# Battery-Switch.net
KiCad netlist of a schematic drawn in Altium Designer
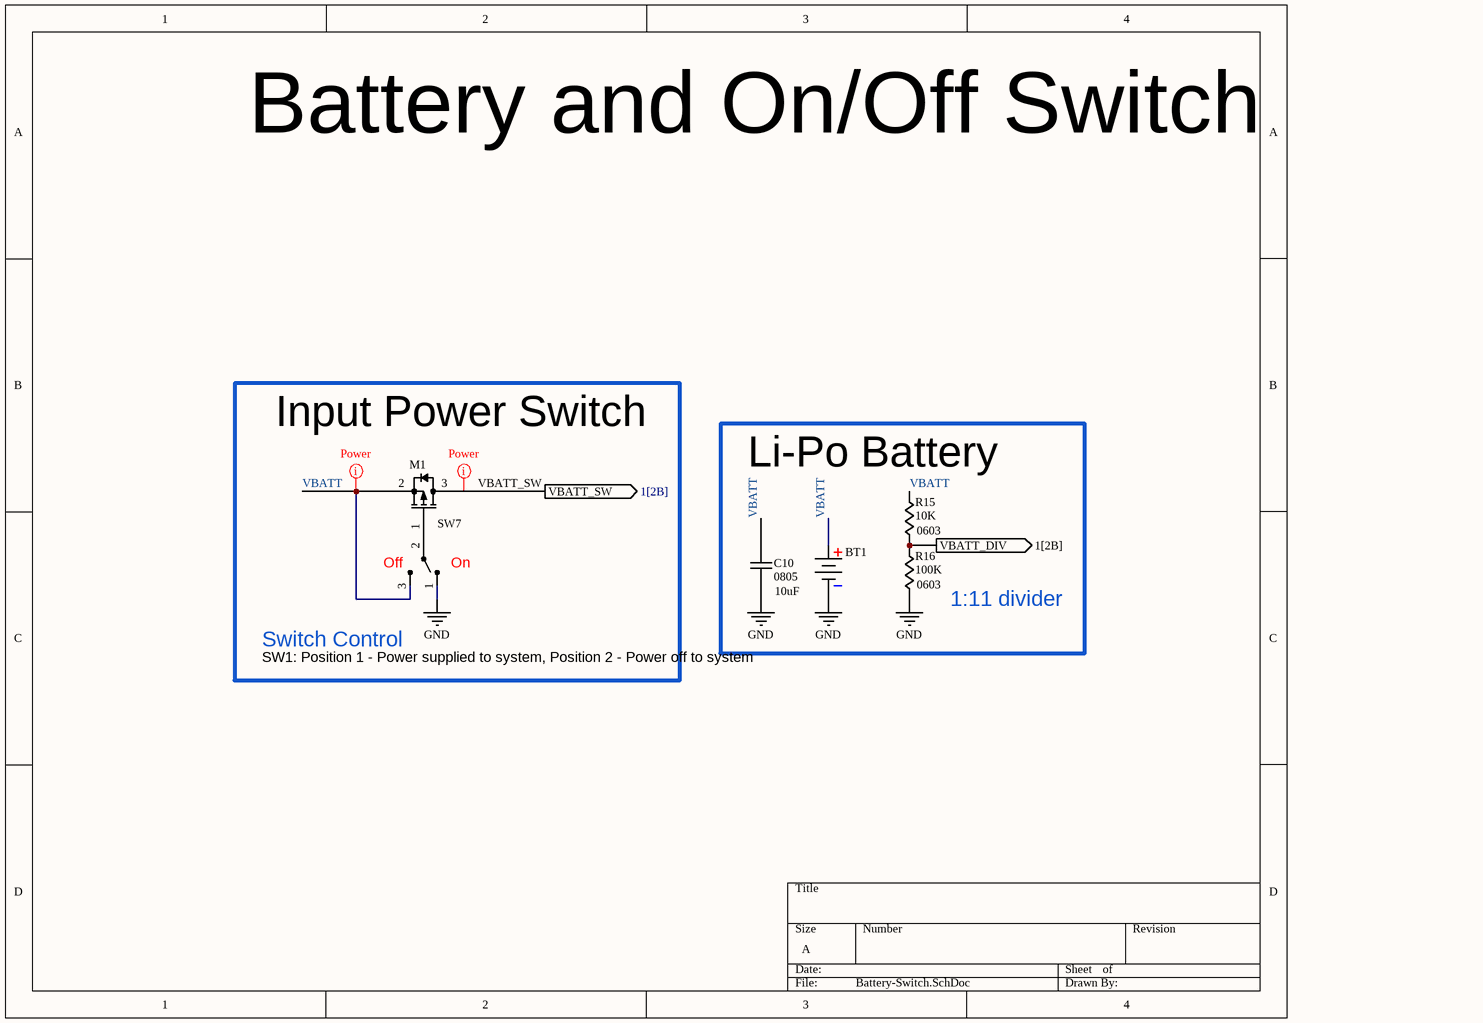
[diagram p0: Battery-Switch.SchDoc]

(export (version "E")
  (design (tool "Eeschema 10.0.6"))
  (components
    (comp (ref "BT1")
      (value "BATT-JST-S2BPHSM4TBLFSN")
      (footprint "PCB-CONN-JST- S2B-PH-SM4-TB(LF)(SN)-2_V")
      (libsource (lib "Animal Inspired Movement and Robotics Lab (AIMRL)") (part "SCH-BATT-JST-S2BPHSM4TBLFSN"))
    )
    (comp (ref "C10")
      (value "10uF")
      (footprint "0805")
      (description "Generic (no part number) 0805 surface mount resistor")
      (fields (field (name "Comment") "CAP-SMD-0805"))
      (libsource (lib "Animal Inspired Movement and Robotics Lab (AIMRL)") (part "SCH-CAP-SMD-0805"))
    )
    (comp (ref "M1")
      (value "TR-MOSFET-P-CH-SOT-23-GENERIC")
      (footprint "PCB-SOT-23")
      (description "MOSFET P-CH 20V 1.3A SOT-23")
      (libsource (lib "Animal Inspired Movement and Robotics Lab (AIMRL)") (part "SCH-TR-MOSFET-P-CH"))
    )
    (comp (ref "R15")
      (value "10K")
      (footprint "0603")
      (description "Generic (no part number) 0603 surface mount resistor")
      (fields (field (name "Comment") "RES-SMD-0603"))
      (libsource (lib "Animal Inspired Movement and Robotics Lab (AIMRL)") (part "SCH-RES-SMD-0603"))
    )
    (comp (ref "R16")
      (value "100K")
      (footprint "0603")
      (description "Generic (no part number) 0603 surface mount resistor")
      (fields (field (name "Comment") "RES-SMD-0603"))
      (libsource (lib "Animal Inspired Movement and Robotics Lab (AIMRL)") (part "SCH-RES-SMD-0603"))
    )
    (comp (ref "SW7")
      (value "SWITCH-SPDT-SMD-SSSS811101")
      (footprint "PCB-SPDT_SMT_SSSS811101")
      (description "Toggle switch")
      (fields
        (field (name "LIBRARYNAME") "Adafruit PyGamer")
        (field (name "SOURCE") "Adafruit PyGamer.SCHLIB")
      )
      (libsource (lib "Animal Inspired Movement and Robotics Lab (AIMRL)") (part "SCH-SWITCH_SPDT"))
    )
  )
  (nets
    (net (code "1") (name "/VBATT") (class "Default")
      (node (ref "BT1") (pin "1") (pinfunction "1_1") (pintype "passive"))
      (node (ref "C10") (pin "2") (pinfunction "2_2") (pintype "passive"))
      (node (ref "M1") (pin "2") (pinfunction "S_2") (pintype "passive"))
      (node (ref "R15") (pin "1") (pinfunction "1_1") (pintype "passive"))
      (node (ref "SW7") (pin "3") (pinfunction "3_3") (pintype "passive"))
    )
    (net (code "2") (name "/VBATT_DIV") (class "Default")
      (node (ref "R15") (pin "2") (pinfunction "2_2") (pintype "passive"))
      (node (ref "R16") (pin "1") (pinfunction "1_1") (pintype "passive"))
    )
    (net (code "3") (name "/VBATT_SW") (class "Default")
      (node (ref "M1") (pin "3") (pinfunction "D_3") (pintype "passive"))
    )
    (net (code "4") (name "GND") (class "Default")
      (node (ref "BT1") (pin "2") (pinfunction "2_2") (pintype "passive"))
      (node (ref "C10") (pin "1") (pinfunction "1_1") (pintype "passive"))
      (node (ref "R16") (pin "2") (pinfunction "2_2") (pintype "passive"))
      (node (ref "SW7") (pin "1") (pinfunction "1_1") (pintype "passive"))
    )
    (net (code "5") (name "Net-(M1-G)") (class "Default")
      (node (ref "M1") (pin "1") (pinfunction "G_1") (pintype "passive"))
      (node (ref "SW7") (pin "2") (pinfunction "2_2") (pintype "passive"))
    )
    (net (code "6") (name "unconnected-(BT1-PadMP1)") (class "Default")
      (node (ref "BT1") (pin "MP1") (pinfunction "MP1_MP1") (pintype "passive"))
    )
    (net (code "7") (name "unconnected-(BT1-PadMP2)") (class "Default")
      (node (ref "BT1") (pin "MP2") (pinfunction "MP2_MP2") (pintype "passive"))
    )
  )
)
